# sensor.net
KiCad netlist of a schematic drawn in EAGLE
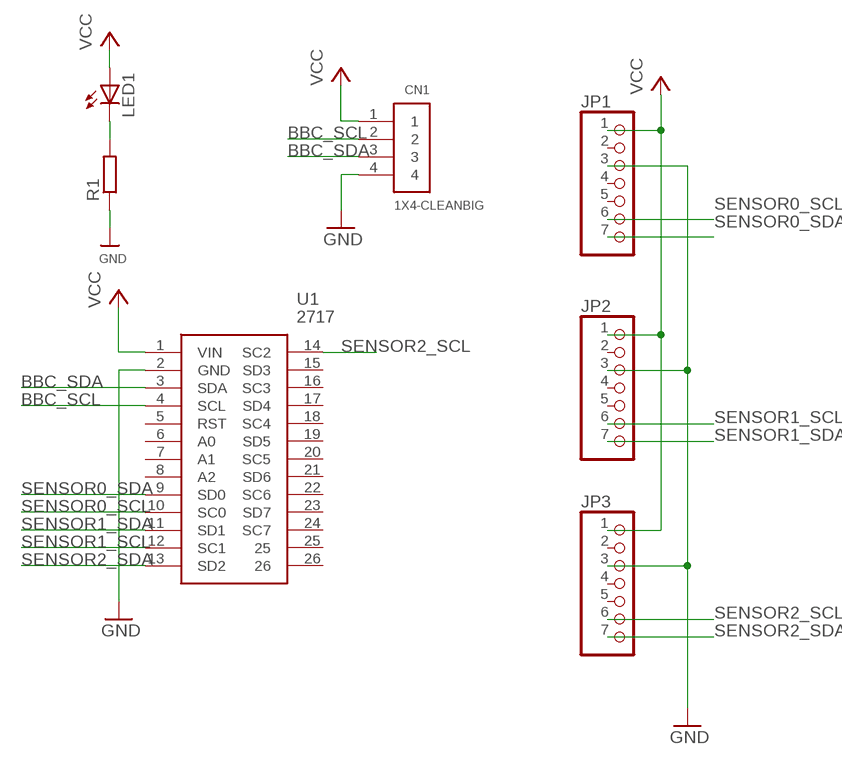
[diagram p0: schematic, sheet 1]

(export (version "E")
  (design (tool "Eeschema 10.0.6"))
  (components
    (comp (ref "CN1")
      (value "1X4-CLEANBIG")
      (footprint "eagle-import:1X04-CLEANBIG")
      (libsource (lib "eagle-import") (part "1X4-CLEANBIG"))
    )
    (comp (ref "JP1")
      (value "MICROBUILDER_HEADER-1X7")
      (footprint "eagle-import:MICROBUILDER_1X07_OVAL")
      (libsource (lib "eagle-import") (part "MICROBUILDER_HEADER-1X7"))
    )
    (comp (ref "JP2")
      (value "MICROBUILDER_HEADER-1X7")
      (footprint "eagle-import:MICROBUILDER_1X07_OVAL")
      (libsource (lib "eagle-import") (part "MICROBUILDER_HEADER-1X7"))
    )
    (comp (ref "JP3")
      (value "MICROBUILDER_HEADER-1X7")
      (footprint "eagle-import:MICROBUILDER_1X07_OVAL")
      (libsource (lib "eagle-import") (part "MICROBUILDER_HEADER-1X7"))
    )
    (comp (ref "LED1")
      (value "LED3MM")
      (footprint "eagle-import:LED3MM")
      (libsource (lib "eagle-import") (part "LED3MM"))
    )
    (comp (ref "R1")
      (value "R-EU_0204/7")
      (footprint "eagle-import:0204_7")
      (libsource (lib "eagle-import") (part "R-EU_0204/7"))
    )
    (comp (ref "U1")
      (value "2717")
      (footprint "eagle-import:2717")
      (fields (field (name "MOUSER_PART_NUMBER") "485-2717"))
      (libsource (lib "eagle-import") (part "2717"))
    )
  )
  (nets
    (net (code "1") (name "/BBC_SCL") (class "Default")
      (node (ref "CN1") (pin "2") (pinfunction "2_2") (pintype "bidirectional"))
      (node (ref "U1") (pin "4") (pinfunction "SCL_4") (pintype "bidirectional"))
    )
    (net (code "2") (name "/BBC_SDA") (class "Default")
      (node (ref "CN1") (pin "3") (pinfunction "3_3") (pintype "bidirectional"))
      (node (ref "U1") (pin "3") (pinfunction "SDA_3") (pintype "bidirectional"))
    )
    (net (code "3") (name "/SENSOR0_SCL") (class "Default")
      (node (ref "JP1") (pin "6") (pinfunction "6_6") (pintype "passive"))
      (node (ref "U1") (pin "10") (pinfunction "SC0_10") (pintype "bidirectional"))
    )
    (net (code "4") (name "/SENSOR0_SDA") (class "Default")
      (node (ref "JP1") (pin "7") (pinfunction "7_7") (pintype "passive"))
      (node (ref "U1") (pin "9") (pinfunction "SD0_9") (pintype "bidirectional"))
    )
    (net (code "5") (name "/SENSOR1_SCL") (class "Default")
      (node (ref "JP2") (pin "6") (pinfunction "6_6") (pintype "passive"))
      (node (ref "U1") (pin "12") (pinfunction "SC1_12") (pintype "bidirectional"))
    )
    (net (code "6") (name "/SENSOR1_SDA") (class "Default")
      (node (ref "JP2") (pin "7") (pinfunction "7_7") (pintype "passive"))
      (node (ref "U1") (pin "11") (pinfunction "SD1_11") (pintype "bidirectional"))
    )
    (net (code "7") (name "/SENSOR2_SCL") (class "Default")
      (node (ref "JP3") (pin "6") (pinfunction "6_6") (pintype "passive"))
      (node (ref "U1") (pin "14") (pinfunction "SC2_14") (pintype "bidirectional"))
    )
    (net (code "8") (name "/SENSOR2_SDA") (class "Default")
      (node (ref "JP3") (pin "7") (pinfunction "7_7") (pintype "passive"))
      (node (ref "U1") (pin "13") (pinfunction "SD2_13") (pintype "bidirectional"))
    )
    (net (code "9") (name "GND") (class "Default")
      (node (ref "CN1") (pin "4") (pinfunction "4_4") (pintype "bidirectional"))
      (node (ref "JP1") (pin "3") (pinfunction "3_3") (pintype "passive"))
      (node (ref "JP2") (pin "3") (pinfunction "3_3") (pintype "passive"))
      (node (ref "JP3") (pin "3") (pinfunction "3_3") (pintype "passive"))
      (node (ref "R1") (pin "1") (pinfunction "1_1") (pintype "passive"))
      (node (ref "U1") (pin "2") (pinfunction "GND_2") (pintype "bidirectional"))
    )
    (net (code "10") (name "Net-(LED1-C)") (class "Default")
      (node (ref "LED1") (pin "K") (pinfunction "C_K") (pintype "passive"))
      (node (ref "R1") (pin "2") (pinfunction "2_2") (pintype "passive"))
    )
    (net (code "11") (name "VCC") (class "Default")
      (node (ref "CN1") (pin "1") (pinfunction "1_1") (pintype "bidirectional"))
      (node (ref "JP1") (pin "1") (pinfunction "1_1") (pintype "passive"))
      (node (ref "JP2") (pin "1") (pinfunction "1_1") (pintype "passive"))
      (node (ref "JP3") (pin "1") (pinfunction "1_1") (pintype "passive"))
      (node (ref "LED1") (pin "A") (pinfunction "A_A") (pintype "passive"))
      (node (ref "U1") (pin "1") (pinfunction "VIN_1") (pintype "bidirectional"))
    )
    (net (code "12") (name "unconnected-(JP1-Pad2)") (class "Default")
      (node (ref "JP1") (pin "2") (pinfunction "2_2") (pintype "passive"))
    )
    (net (code "13") (name "unconnected-(JP1-Pad4)") (class "Default")
      (node (ref "JP1") (pin "4") (pinfunction "4_4") (pintype "passive"))
    )
    (net (code "14") (name "unconnected-(JP1-Pad5)") (class "Default")
      (node (ref "JP1") (pin "5") (pinfunction "5_5") (pintype "passive"))
    )
    (net (code "15") (name "unconnected-(JP2-Pad2)") (class "Default")
      (node (ref "JP2") (pin "2") (pinfunction "2_2") (pintype "passive"))
    )
    (net (code "16") (name "unconnected-(JP2-Pad4)") (class "Default")
      (node (ref "JP2") (pin "4") (pinfunction "4_4") (pintype "passive"))
    )
    (net (code "17") (name "unconnected-(JP2-Pad5)") (class "Default")
      (node (ref "JP2") (pin "5") (pinfunction "5_5") (pintype "passive"))
    )
    (net (code "18") (name "unconnected-(JP3-Pad2)") (class "Default")
      (node (ref "JP3") (pin "2") (pinfunction "2_2") (pintype "passive"))
    )
    (net (code "19") (name "unconnected-(JP3-Pad4)") (class "Default")
      (node (ref "JP3") (pin "4") (pinfunction "4_4") (pintype "passive"))
    )
    (net (code "20") (name "unconnected-(JP3-Pad5)") (class "Default")
      (node (ref "JP3") (pin "5") (pinfunction "5_5") (pintype "passive"))
    )
    (net (code "21") (name "unconnected-(U1-A0-Pad6)") (class "Default")
      (node (ref "U1") (pin "6") (pinfunction "A0_6") (pintype "bidirectional"))
    )
    (net (code "22") (name "unconnected-(U1-A1-Pad7)") (class "Default")
      (node (ref "U1") (pin "7") (pinfunction "A1_7") (pintype "bidirectional"))
    )
    (net (code "23") (name "unconnected-(U1-A2-Pad8)") (class "Default")
      (node (ref "U1") (pin "8") (pinfunction "A2_8") (pintype "bidirectional"))
    )
    (net (code "24") (name "unconnected-(U1-Pad25)") (class "Default")
      (node (ref "U1") (pin "25") (pinfunction "25_25") (pintype "bidirectional"))
    )
    (net (code "25") (name "unconnected-(U1-Pad26)") (class "Default")
      (node (ref "U1") (pin "26") (pinfunction "26_26") (pintype "bidirectional"))
    )
    (net (code "26") (name "unconnected-(U1-RST-Pad5)") (class "Default")
      (node (ref "U1") (pin "5") (pinfunction "RST_5") (pintype "bidirectional"))
    )
    (net (code "27") (name "unconnected-(U1-SC3-Pad16)") (class "Default")
      (node (ref "U1") (pin "16") (pinfunction "SC3_16") (pintype "bidirectional"))
    )
    (net (code "28") (name "unconnected-(U1-SC4-Pad18)") (class "Default")
      (node (ref "U1") (pin "18") (pinfunction "SC4_18") (pintype "bidirectional"))
    )
    (net (code "29") (name "unconnected-(U1-SC5-Pad20)") (class "Default")
      (node (ref "U1") (pin "20") (pinfunction "SC5_20") (pintype "bidirectional"))
    )
    (net (code "30") (name "unconnected-(U1-SC6-Pad22)") (class "Default")
      (node (ref "U1") (pin "22") (pinfunction "SC6_22") (pintype "bidirectional"))
    )
    (net (code "31") (name "unconnected-(U1-SC7-Pad24)") (class "Default")
      (node (ref "U1") (pin "24") (pinfunction "SC7_24") (pintype "bidirectional"))
    )
    (net (code "32") (name "unconnected-(U1-SD3-Pad15)") (class "Default")
      (node (ref "U1") (pin "15") (pinfunction "SD3_15") (pintype "bidirectional"))
    )
    (net (code "33") (name "unconnected-(U1-SD4-Pad17)") (class "Default")
      (node (ref "U1") (pin "17") (pinfunction "SD4_17") (pintype "bidirectional"))
    )
    (net (code "34") (name "unconnected-(U1-SD5-Pad19)") (class "Default")
      (node (ref "U1") (pin "19") (pinfunction "SD5_19") (pintype "bidirectional"))
    )
    (net (code "35") (name "unconnected-(U1-SD6-Pad21)") (class "Default")
      (node (ref "U1") (pin "21") (pinfunction "SD6_21") (pintype "bidirectional"))
    )
    (net (code "36") (name "unconnected-(U1-SD7-Pad23)") (class "Default")
      (node (ref "U1") (pin "23") (pinfunction "SD7_23") (pintype "bidirectional"))
    )
  )
)
